# PCB_for_ADXL345.net
KiCad netlist of a schematic drawn in EAGLE
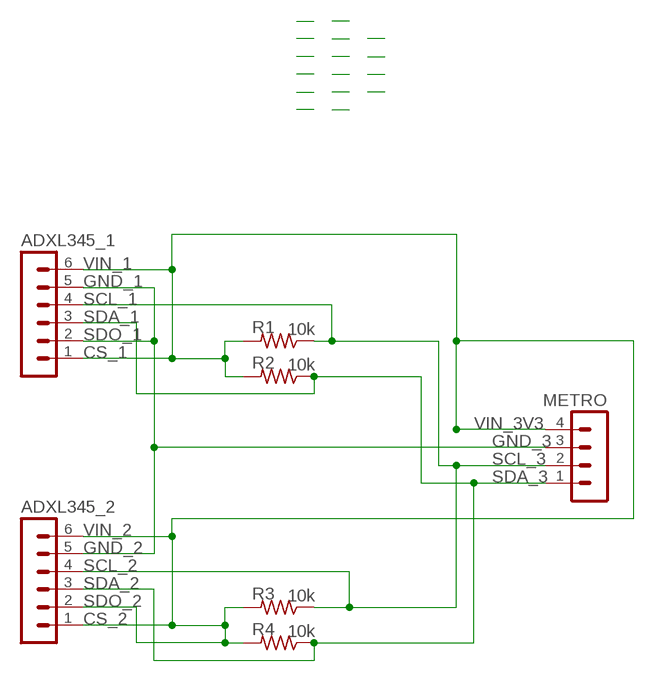
[diagram p0: schematic, sheet 1]

(export (version "E")
  (design (tool "Eeschema 10.0.6"))
  (components
    (comp (ref "ADXL345_1")
      (value "MA06-1")
      (footprint "eagle-import:MA06-1")
      (libsource (lib "eagle-import") (part "MA06-1"))
    )
    (comp (ref "ADXL345_2")
      (value "MA06-1")
      (footprint "eagle-import:MA06-1")
      (libsource (lib "eagle-import") (part "MA06-1"))
    )
    (comp (ref "METRO")
      (value "MA04-1")
      (footprint "eagle-import:MA04-1")
      (libsource (lib "eagle-import") (part "MA04-1"))
    )
    (comp (ref "R1")
      (value "10k")
      (footprint "eagle-import:0207_10")
      (libsource (lib "eagle-import") (part "R-US_0207/10"))
    )
    (comp (ref "R2")
      (value "10k")
      (footprint "eagle-import:0207_10")
      (libsource (lib "eagle-import") (part "R-US_0207/10"))
    )
    (comp (ref "R3")
      (value "10k")
      (footprint "eagle-import:0207_10")
      (libsource (lib "eagle-import") (part "R-US_0207/10"))
    )
    (comp (ref "R4")
      (value "10k")
      (footprint "eagle-import:0207_10")
      (libsource (lib "eagle-import") (part "R-US_0207/10"))
    )
  )
  (nets
    (net (code "17") (name "Net-(ADXL345_1-Pad1)") (class "Default")
      (node (ref "ADXL345_1") (pin "1") (pinfunction "1_1") (pintype "passive"))
      (node (ref "ADXL345_1") (pin "6") (pinfunction "6_6") (pintype "passive"))
      (node (ref "ADXL345_2") (pin "1") (pinfunction "1_1") (pintype "passive"))
      (node (ref "ADXL345_2") (pin "2") (pinfunction "2_2") (pintype "passive"))
      (node (ref "ADXL345_2") (pin "6") (pinfunction "6_6") (pintype "passive"))
      (node (ref "METRO") (pin "4") (pinfunction "4_4") (pintype "passive"))
      (node (ref "R1") (pin "2") (pinfunction "2_2") (pintype "passive"))
      (node (ref "R2") (pin "2") (pinfunction "2_2") (pintype "passive"))
      (node (ref "R3") (pin "2") (pinfunction "2_2") (pintype "passive"))
      (node (ref "R4") (pin "2") (pinfunction "2_2") (pintype "passive"))
    )
    (net (code "18") (name "Net-(ADXL345_1-Pad2)") (class "Default")
      (node (ref "ADXL345_1") (pin "2") (pinfunction "2_2") (pintype "passive"))
      (node (ref "ADXL345_1") (pin "5") (pinfunction "5_5") (pintype "passive"))
      (node (ref "ADXL345_2") (pin "5") (pinfunction "5_5") (pintype "passive"))
      (node (ref "METRO") (pin "3") (pinfunction "3_3") (pintype "passive"))
    )
    (net (code "19") (name "Net-(ADXL345_1-Pad3)") (class "Default")
      (node (ref "ADXL345_1") (pin "3") (pinfunction "3_3") (pintype "passive"))
      (node (ref "ADXL345_2") (pin "3") (pinfunction "3_3") (pintype "passive"))
      (node (ref "METRO") (pin "1") (pinfunction "1_1") (pintype "passive"))
      (node (ref "R2") (pin "1") (pinfunction "1_1") (pintype "passive"))
      (node (ref "R4") (pin "1") (pinfunction "1_1") (pintype "passive"))
    )
    (net (code "20") (name "Net-(ADXL345_1-Pad4)") (class "Default")
      (node (ref "ADXL345_1") (pin "4") (pinfunction "4_4") (pintype "passive"))
      (node (ref "ADXL345_2") (pin "4") (pinfunction "4_4") (pintype "passive"))
      (node (ref "METRO") (pin "2") (pinfunction "2_2") (pintype "passive"))
      (node (ref "R1") (pin "1") (pinfunction "1_1") (pintype "passive"))
      (node (ref "R3") (pin "1") (pinfunction "1_1") (pintype "passive"))
    )
  )
)
